# adapter.net
KiCad netlist of a schematic drawn in EAGLE
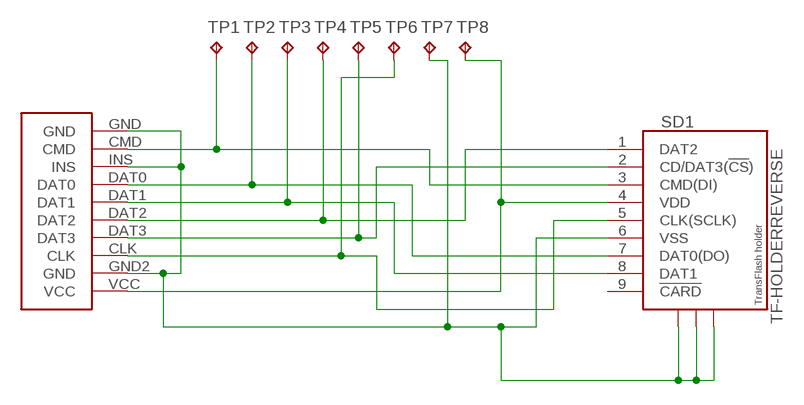
[diagram p0: schematic, sheet 1]

(export (version "E")
  (design (tool "Eeschema 10.0.6"))
  (components
    (comp (ref "SD1")
      (value "TF-HOLDERREVERSE")
      (footprint "eagle-import:TF-PULL-REVERSE")
      (libsource (lib "eagle-import") (part "TF-HOLDERREVERSE"))
    )
    (comp (ref "TP1")
      (value "TPTP20R")
      (footprint "eagle-import:TP20R")
      (libsource (lib "eagle-import") (part "TPTP20R"))
    )
    (comp (ref "TP2")
      (value "TPTP20R")
      (footprint "eagle-import:TP20R")
      (libsource (lib "eagle-import") (part "TPTP20R"))
    )
    (comp (ref "TP3")
      (value "TPTP20R")
      (footprint "eagle-import:TP20R")
      (libsource (lib "eagle-import") (part "TPTP20R"))
    )
    (comp (ref "TP4")
      (value "TPTP20R")
      (footprint "eagle-import:TP20R")
      (libsource (lib "eagle-import") (part "TPTP20R"))
    )
    (comp (ref "TP5")
      (value "TPTP20R")
      (footprint "eagle-import:TP20R")
      (libsource (lib "eagle-import") (part "TPTP20R"))
    )
    (comp (ref "TP6")
      (value "TPTP20R")
      (footprint "eagle-import:TP20R")
      (libsource (lib "eagle-import") (part "TPTP20R"))
    )
    (comp (ref "TP7")
      (value "TPTP20R")
      (footprint "eagle-import:TP20R")
      (libsource (lib "eagle-import") (part "TPTP20R"))
    )
    (comp (ref "TP8")
      (value "TPTP20R")
      (footprint "eagle-import:TP20R")
      (libsource (lib "eagle-import") (part "TPTP20R"))
    )
    (comp (ref "U$1")
      (value "CONNECTOR")
      (footprint "eagle-import:CONNECTOR")
      (libsource (lib "eagle-import") (part "CONNECTOR"))
    )
  )
  (nets
    (net (code "1") (name "Net-(SD1-CD{slash}DAT3(~{CS}))") (class "Default")
      (node (ref "SD1") (pin "2") (pinfunction "CD/DAT3(~{CS})_2") (pintype "bidirectional"))
      (node (ref "TP5") (pin "TP") (pinfunction "TP_TP") (pintype "input"))
      (node (ref "U$1") (pin "DAT3") (pinfunction "DAT3_DAT3") (pintype "bidirectional"))
    )
    (net (code "2") (name "Net-(SD1-CLK(SCLK))") (class "Default")
      (node (ref "SD1") (pin "5") (pinfunction "CLK(SCLK)_5") (pintype "input"))
      (node (ref "TP6") (pin "TP") (pinfunction "TP_TP") (pintype "input"))
      (node (ref "U$1") (pin "CLK") (pinfunction "CLK_CLK") (pintype "bidirectional"))
    )
    (net (code "3") (name "Net-(SD1-CMD(DI))") (class "Default")
      (node (ref "SD1") (pin "3") (pinfunction "CMD(DI)_3") (pintype "bidirectional"))
      (node (ref "TP1") (pin "TP") (pinfunction "TP_TP") (pintype "input"))
      (node (ref "U$1") (pin "CMD") (pinfunction "CMD_CMD") (pintype "bidirectional"))
    )
    (net (code "4") (name "Net-(SD1-DAT0(DO))") (class "Default")
      (node (ref "SD1") (pin "7") (pinfunction "DAT0(DO)_7") (pintype "bidirectional"))
      (node (ref "TP2") (pin "TP") (pinfunction "TP_TP") (pintype "input"))
      (node (ref "U$1") (pin "DAT0") (pinfunction "DAT0_DAT0") (pintype "bidirectional"))
    )
    (net (code "5") (name "Net-(SD1-DAT1)") (class "Default")
      (node (ref "SD1") (pin "8") (pinfunction "DAT1_8") (pintype "bidirectional"))
      (node (ref "TP3") (pin "TP") (pinfunction "TP_TP") (pintype "input"))
      (node (ref "U$1") (pin "DAT1") (pinfunction "DAT1_DAT1") (pintype "bidirectional"))
    )
    (net (code "6") (name "Net-(SD1-DAT2)") (class "Default")
      (node (ref "SD1") (pin "1") (pinfunction "DAT2_1") (pintype "bidirectional"))
      (node (ref "TP4") (pin "TP") (pinfunction "TP_TP") (pintype "input"))
      (node (ref "U$1") (pin "DAT2") (pinfunction "DAT2_DAT2") (pintype "bidirectional"))
    )
    (net (code "7") (name "Net-(SD1-VDD)") (class "Default")
      (node (ref "SD1") (pin "4") (pinfunction "VDD_4") (pintype "power_in"))
      (node (ref "TP8") (pin "TP") (pinfunction "TP_TP") (pintype "input"))
      (node (ref "U$1") (pin "VCC") (pinfunction "VCC_VCC") (pintype "power_in"))
    )
    (net (code "8") (name "Net-(SD1-VSS)") (class "Default")
      (node (ref "SD1") (pin "6") (pinfunction "VSS_6") (pintype "power_in"))
      (node (ref "SD1") (pin "S1") (pinfunction "S1_S1") (pintype "passive"))
      (node (ref "SD1") (pin "S2") (pinfunction "S2_S2") (pintype "passive"))
      (node (ref "SD1") (pin "S3") (pinfunction "S3_S3") (pintype "passive"))
      (node (ref "TP7") (pin "TP") (pinfunction "TP_TP") (pintype "input"))
      (node (ref "U$1") (pin "GND") (pinfunction "GND_GND") (pintype "power_in"))
      (node (ref "U$1") (pin "GND2") (pinfunction "GND_GND2") (pintype "power_in"))
      (node (ref "U$1") (pin "INS") (pinfunction "INS_INS") (pintype "bidirectional"))
    )
    (net (code "9") (name "unconnected-(SD1-~{CARD}-Pad9)") (class "Default")
      (node (ref "SD1") (pin "9") (pinfunction "~{CARD}_9") (pintype "passive"))
    )
  )
)
